# S3A6_Output_Signal_s_v1p00.net
KiCad netlist of a schematic drawn in EAGLE
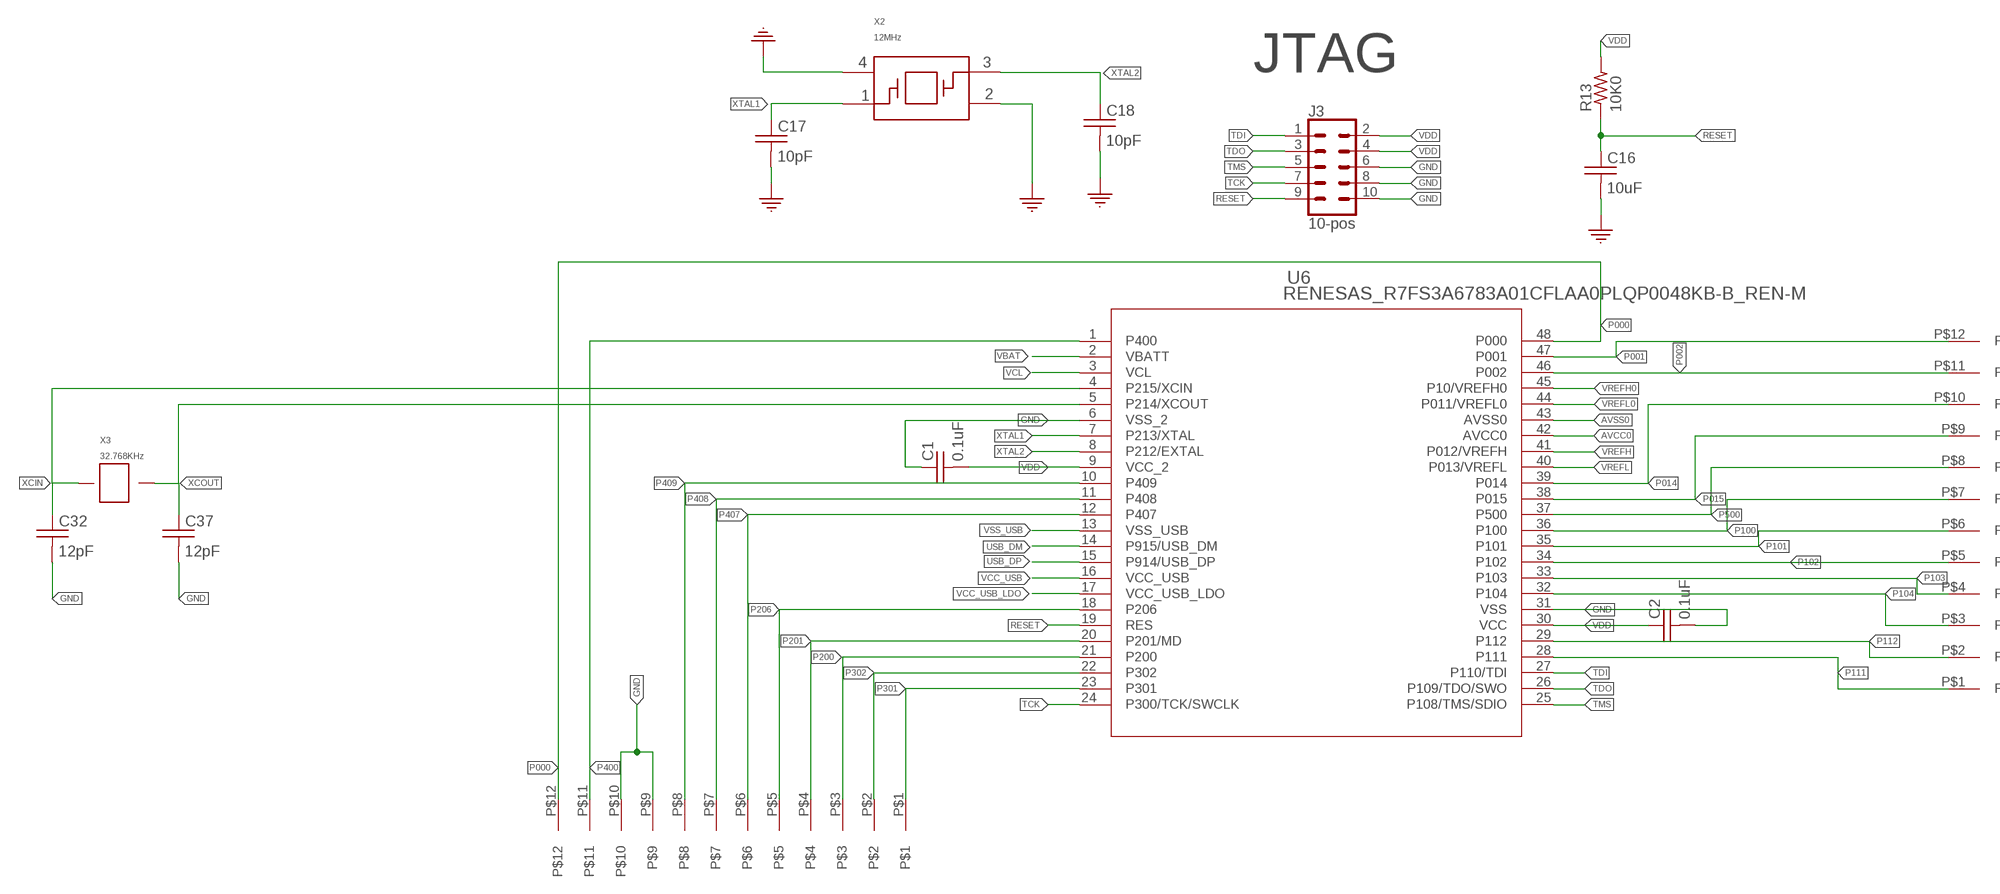
[diagram p0: schematic, sheet 1, part 1 of 2]
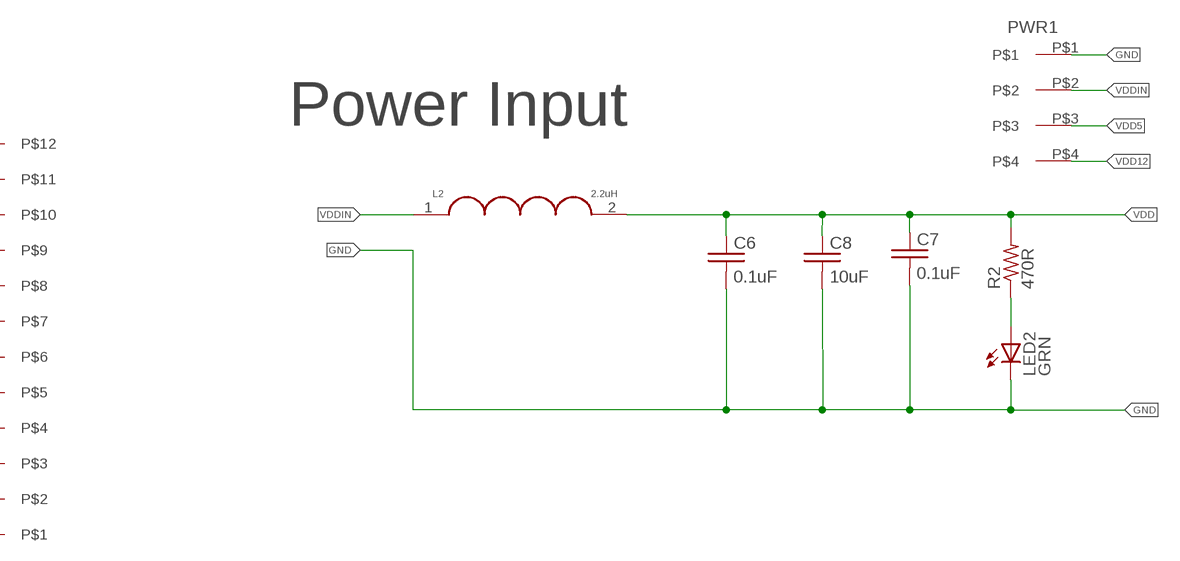
[diagram p1: schematic, sheet 1, part 2 of 2]

(export (version "E")
  (design (tool "Eeschema 10.0.6"))
  (components
    (comp (ref "C1")
      (value "0.1uF")
      (footprint "eagle-import:0402")
      (fields (field (name "PARTNO") "CL05F104ZO5NNNC"))
      (libsource (lib "eagle-import") (part "C_0402_0.1UF"))
    )
    (comp (ref "C2")
      (value "0.1uF")
      (footprint "eagle-import:0402")
      (fields (field (name "PARTNO") "CL05F104ZO5NNNC"))
      (libsource (lib "eagle-import") (part "C_0402_0.1UF"))
    )
    (comp (ref "C6")
      (value "0.1uF")
      (footprint "eagle-import:0402")
      (libsource (lib "eagle-import") (part "C_0402"))
    )
    (comp (ref "C7")
      (value "0.1uF")
      (footprint "eagle-import:0402")
      (libsource (lib "eagle-import") (part "C_0402"))
    )
    (comp (ref "C8")
      (value "10uF")
      (footprint "eagle-import:0402")
      (libsource (lib "eagle-import") (part "C_0402"))
    )
    (comp (ref "C16")
      (value "10uF")
      (footprint "eagle-import:0402")
      (fields (field (name "PARTNO") "CL05A106MP8NUB8"))
      (libsource (lib "eagle-import") (part "C_0402_10UF"))
    )
    (comp (ref "C17")
      (value "10pF")
      (footprint "eagle-import:0402")
      (fields (field (name "PARTNO") "UMK105CG180JV-F"))
      (libsource (lib "eagle-import") (part "C_0402_18PF"))
    )
    (comp (ref "C18")
      (value "10pF")
      (footprint "eagle-import:0402")
      (fields (field (name "PARTNO") "UMK105CG180JV-F"))
      (libsource (lib "eagle-import") (part "C_0402_18PF"))
    )
    (comp (ref "C32")
      (value "12pF")
      (footprint "eagle-import:0402")
      (fields (field (name "PARTNO") "CL05C120JB5NNNC"))
      (libsource (lib "eagle-import") (part "C_0402_12PF"))
    )
    (comp (ref "C37")
      (value "12pF")
      (footprint "eagle-import:0402")
      (fields (field (name "PARTNO") "CL05C120JB5NNNC"))
      (libsource (lib "eagle-import") (part "C_0402_12PF"))
    )
    (comp (ref "J3")
      (value "10-pos")
      (footprint "eagle-import:2X5")
      (fields (field (name "PARTNO") "PH2RA-10-UA"))
      (libsource (lib "eagle-import") (part "CONN_05X2_RAPTH"))
    )
    (comp (ref "L2")
      (value "2.2uH")
      (footprint "eagle-import:1008_(2520_METRIC)")
      (libsource (lib "eagle-import") (part "INDUCTOR_1008_2.2_MH_1.3A"))
    )
    (comp (ref "LED2")
      (value "LED_0805_GREEN")
      (footprint "eagle-import:LED_0805_GREEN")
      (libsource (lib "eagle-import") (part "LED_0805_GREEN"))
    )
    (comp (ref "PWR1")
      (value "4-pos")
      (footprint "eagle-import:1X4_3.81MM_PITCH")
      (fields (field (name "PARTNO") "691322310004"))
      (libsource (lib "eagle-import") (part "3.81MM_1_X_4_RT_ANGLE_PLUG_HEADER"))
    )
    (comp (ref "R2")
      (value "470R")
      (footprint "eagle-import:0402")
      (libsource (lib "eagle-import") (part "R_0402"))
    )
    (comp (ref "R13")
      (value "10K0")
      (footprint "eagle-import:0402")
      (fields (field (name "PARTNO") "RMCF0402JT10K0"))
      (libsource (lib "eagle-import") (part "R_0402_10K0"))
    )
    (comp (ref "U$1")
      (value "1_X_12_HEADER_GENERIC_.1INCH")
      (footprint "eagle-import:HEADER_1_X_12_.1_INCH")
      (libsource (lib "eagle-import") (part "1_X_12_HEADER_GENERIC_.1INCH"))
    )
    (comp (ref "U$2")
      (value "1_X_12_HEADER_GENERIC_.1INCH")
      (footprint "eagle-import:HEADER_1_X_12_.1_INCH")
      (libsource (lib "eagle-import") (part "1_X_12_HEADER_GENERIC_.1INCH"))
    )
    (comp (ref "U6")
      (value "RENESAS_R7FS3A6783A01CFLAA0PLQP0048KB-B_REN-M")
      (footprint "eagle-import:PLQP0048KB-B_REN-M")
      (fields
        (field (name "MANUFACTURER_PART_NUMBER") "R7FS3A6783A01CFL#AA0")
        (field (name "COPYRIGHT") "Copyright (C) 2021 Accelerated Designs. All rights reserved")
      )
      (libsource (lib "eagle-import") (part "RENESAS_R7FS3A6783A01CFLAA0PLQP0048KB-B_REN-M"))
    )
    (comp (ref "X2")
      (value "12MHz")
      (footprint "eagle-import:SMD_3225")
      (fields (field (name "PARTNO") "FA-238 24.0000MB-C3 "))
      (libsource (lib "eagle-import") (part "XTAL_24_MHZ"))
    )
    (comp (ref "X3")
      (value "32.768KHz")
      (footprint "eagle-import:SMD_X_2_PADS")
      (fields (field (name "PARTNO") "ABS07-32.768KHZ-T"))
      (libsource (lib "eagle-import") (part "XTAL_32.768KHZ"))
    )
  )
  (nets
    (net (code "1") (name "AVCC0") (class "Default")
      (node (ref "U6") (pin "42") (pinfunction "AVCC0_42") (pintype "power_in"))
    )
    (net (code "2") (name "AVSS0") (class "Default")
      (node (ref "U6") (pin "43") (pinfunction "AVSS0_43") (pintype "passive"))
    )
    (net (code "3") (name "GND") (class "Default")
      (node (ref "C1") (pin "P$1") (pinfunction "1_P$1") (pintype "passive"))
      (node (ref "C16") (pin "P$2") (pinfunction "2_P$2") (pintype "passive"))
      (node (ref "C17") (pin "P$2") (pinfunction "2_P$2") (pintype "passive"))
      (node (ref "C18") (pin "P$2") (pinfunction "2_P$2") (pintype "passive"))
      (node (ref "C2") (pin "P$2") (pinfunction "2_P$2") (pintype "passive"))
      (node (ref "C32") (pin "P$2") (pinfunction "2_P$2") (pintype "passive"))
      (node (ref "C37") (pin "P$2") (pinfunction "2_P$2") (pintype "passive"))
      (node (ref "C6") (pin "P$2") (pinfunction "2_P$2") (pintype "passive"))
      (node (ref "C7") (pin "P$2") (pinfunction "2_P$2") (pintype "passive"))
      (node (ref "C8") (pin "P$2") (pinfunction "2_P$2") (pintype "passive"))
      (node (ref "J3") (pin "10") (pinfunction "10_10") (pintype "passive"))
      (node (ref "J3") (pin "6") (pinfunction "6_6") (pintype "passive"))
      (node (ref "J3") (pin "8") (pinfunction "8_8") (pintype "passive"))
      (node (ref "LED2") (pin "C") (pinfunction "C_C") (pintype "passive"))
      (node (ref "PWR1") (pin "P$1") (pinfunction "P$1_P$1") (pintype "bidirectional"))
      (node (ref "U$1") (pin "P$10") (pinfunction "P$10_P$10") (pintype "bidirectional"))
      (node (ref "U$1") (pin "P$9") (pinfunction "P$9_P$9") (pintype "bidirectional"))
      (node (ref "U6") (pin "31") (pinfunction "VSS_31") (pintype "passive"))
      (node (ref "U6") (pin "6") (pinfunction "VSS_2_6") (pintype "passive"))
      (node (ref "X2") (pin "2") (pinfunction "2_2") (pintype "bidirectional"))
      (node (ref "X2") (pin "4") (pinfunction "4_4") (pintype "bidirectional"))
    )
    (net (code "4") (name "Net-(R2-1)") (class "Default")
      (node (ref "LED2") (pin "A") (pinfunction "A_A") (pintype "passive"))
      (node (ref "R2") (pin "P$1") (pinfunction "1_P$1") (pintype "passive"))
    )
    (net (code "5") (name "P000") (class "Default")
      (node (ref "U$1") (pin "P$12") (pinfunction "P$12_P$12") (pintype "bidirectional"))
      (node (ref "U6") (pin "48") (pinfunction "P000_48") (pintype "bidirectional"))
    )
    (net (code "6") (name "P001") (class "Default")
      (node (ref "U$2") (pin "P$12") (pinfunction "P$12_P$12") (pintype "bidirectional"))
      (node (ref "U6") (pin "47") (pinfunction "P001_47") (pintype "bidirectional"))
    )
    (net (code "7") (name "P002") (class "Default")
      (node (ref "U$2") (pin "P$11") (pinfunction "P$11_P$11") (pintype "bidirectional"))
      (node (ref "U6") (pin "46") (pinfunction "P002_46") (pintype "bidirectional"))
    )
    (net (code "8") (name "P014") (class "Default")
      (node (ref "U$2") (pin "P$10") (pinfunction "P$10_P$10") (pintype "bidirectional"))
      (node (ref "U6") (pin "39") (pinfunction "P014_39") (pintype "bidirectional"))
    )
    (net (code "9") (name "P015") (class "Default")
      (node (ref "U$2") (pin "P$9") (pinfunction "P$9_P$9") (pintype "bidirectional"))
      (node (ref "U6") (pin "38") (pinfunction "P015_38") (pintype "bidirectional"))
    )
    (net (code "10") (name "P100") (class "Default")
      (node (ref "U$2") (pin "P$7") (pinfunction "P$7_P$7") (pintype "bidirectional"))
      (node (ref "U6") (pin "36") (pinfunction "P100_36") (pintype "bidirectional"))
    )
    (net (code "11") (name "P101") (class "Default")
      (node (ref "U$2") (pin "P$6") (pinfunction "P$6_P$6") (pintype "bidirectional"))
      (node (ref "U6") (pin "35") (pinfunction "P101_35") (pintype "bidirectional"))
    )
    (net (code "12") (name "P102") (class "Default")
      (node (ref "U$2") (pin "P$5") (pinfunction "P$5_P$5") (pintype "bidirectional"))
      (node (ref "U6") (pin "34") (pinfunction "P102_34") (pintype "bidirectional"))
    )
    (net (code "13") (name "P103") (class "Default")
      (node (ref "U$2") (pin "P$4") (pinfunction "P$4_P$4") (pintype "bidirectional"))
      (node (ref "U6") (pin "33") (pinfunction "P103_33") (pintype "bidirectional"))
    )
    (net (code "14") (name "P104") (class "Default")
      (node (ref "U$2") (pin "P$3") (pinfunction "P$3_P$3") (pintype "bidirectional"))
      (node (ref "U6") (pin "32") (pinfunction "P104_32") (pintype "bidirectional"))
    )
    (net (code "15") (name "P111") (class "Default")
      (node (ref "U$2") (pin "P$1") (pinfunction "P$1_P$1") (pintype "bidirectional"))
      (node (ref "U6") (pin "28") (pinfunction "P111_28") (pintype "bidirectional"))
    )
    (net (code "16") (name "P112") (class "Default")
      (node (ref "U$2") (pin "P$2") (pinfunction "P$2_P$2") (pintype "bidirectional"))
      (node (ref "U6") (pin "29") (pinfunction "P112_29") (pintype "bidirectional"))
    )
    (net (code "17") (name "P200") (class "Default")
      (node (ref "U$1") (pin "P$3") (pinfunction "P$3_P$3") (pintype "bidirectional"))
      (node (ref "U6") (pin "21") (pinfunction "P200_21") (pintype "bidirectional"))
    )
    (net (code "18") (name "P201") (class "Default")
      (node (ref "U$1") (pin "P$4") (pinfunction "P$4_P$4") (pintype "bidirectional"))
      (node (ref "U6") (pin "20") (pinfunction "P201/MD_20") (pintype "bidirectional"))
    )
    (net (code "19") (name "P206") (class "Default")
      (node (ref "U$1") (pin "P$5") (pinfunction "P$5_P$5") (pintype "bidirectional"))
      (node (ref "U6") (pin "18") (pinfunction "P206_18") (pintype "bidirectional"))
    )
    (net (code "20") (name "P301") (class "Default")
      (node (ref "U$1") (pin "P$1") (pinfunction "P$1_P$1") (pintype "bidirectional"))
      (node (ref "U6") (pin "23") (pinfunction "P301_23") (pintype "bidirectional"))
    )
    (net (code "21") (name "P302") (class "Default")
      (node (ref "U$1") (pin "P$2") (pinfunction "P$2_P$2") (pintype "bidirectional"))
      (node (ref "U6") (pin "22") (pinfunction "P302_22") (pintype "bidirectional"))
    )
    (net (code "22") (name "P400") (class "Default")
      (node (ref "U$1") (pin "P$11") (pinfunction "P$11_P$11") (pintype "bidirectional"))
      (node (ref "U6") (pin "1") (pinfunction "P400_1") (pintype "bidirectional"))
    )
    (net (code "23") (name "P407") (class "Default")
      (node (ref "U$1") (pin "P$6") (pinfunction "P$6_P$6") (pintype "bidirectional"))
      (node (ref "U6") (pin "12") (pinfunction "P407_12") (pintype "bidirectional"))
    )
    (net (code "24") (name "P408") (class "Default")
      (node (ref "U$1") (pin "P$7") (pinfunction "P$7_P$7") (pintype "bidirectional"))
      (node (ref "U6") (pin "11") (pinfunction "P408_11") (pintype "bidirectional"))
    )
    (net (code "25") (name "P409") (class "Default")
      (node (ref "U$1") (pin "P$8") (pinfunction "P$8_P$8") (pintype "bidirectional"))
      (node (ref "U6") (pin "10") (pinfunction "P409_10") (pintype "bidirectional"))
    )
    (net (code "26") (name "P500") (class "Default")
      (node (ref "U$2") (pin "P$8") (pinfunction "P$8_P$8") (pintype "bidirectional"))
      (node (ref "U6") (pin "37") (pinfunction "P500_37") (pintype "bidirectional"))
    )
    (net (code "27") (name "RESET") (class "Default")
      (node (ref "C16") (pin "P$1") (pinfunction "1_P$1") (pintype "passive"))
      (node (ref "J3") (pin "9") (pinfunction "9_9") (pintype "passive"))
      (node (ref "R13") (pin "P$1") (pinfunction "1_P$1") (pintype "passive"))
      (node (ref "U6") (pin "19") (pinfunction "RES_19") (pintype "passive"))
    )
    (net (code "28") (name "TCK") (class "Default")
      (node (ref "J3") (pin "7") (pinfunction "7_7") (pintype "passive"))
      (node (ref "U6") (pin "24") (pinfunction "P300/TCK/SWCLK_24") (pintype "bidirectional"))
    )
    (net (code "29") (name "TDI") (class "Default")
      (node (ref "J3") (pin "1") (pinfunction "1_1") (pintype "passive"))
      (node (ref "U6") (pin "27") (pinfunction "P110/TDI_27") (pintype "bidirectional"))
    )
    (net (code "30") (name "TDO") (class "Default")
      (node (ref "J3") (pin "3") (pinfunction "3_3") (pintype "passive"))
      (node (ref "U6") (pin "26") (pinfunction "P109/TDO/SWO_26") (pintype "bidirectional"))
    )
    (net (code "31") (name "TMS") (class "Default")
      (node (ref "J3") (pin "5") (pinfunction "5_5") (pintype "passive"))
      (node (ref "U6") (pin "25") (pinfunction "P108/TMS/SDIO_25") (pintype "bidirectional"))
    )
    (net (code "32") (name "USB_DM") (class "Default")
      (node (ref "U6") (pin "14") (pinfunction "P915/USB_DM_14") (pintype "bidirectional"))
    )
    (net (code "33") (name "USB_DP") (class "Default")
      (node (ref "U6") (pin "15") (pinfunction "P914/USB_DP_15") (pintype "bidirectional"))
    )
    (net (code "34") (name "VBAT") (class "Default")
      (node (ref "U6") (pin "2") (pinfunction "VBATT_2") (pintype "passive"))
    )
    (net (code "35") (name "VCC_USB") (class "Default")
      (node (ref "U6") (pin "16") (pinfunction "VCC_USB_16") (pintype "power_in"))
    )
    (net (code "36") (name "VCC_USB_LDO") (class "Default")
      (node (ref "U6") (pin "17") (pinfunction "VCC_USB_LDO_17") (pintype "power_in"))
    )
    (net (code "37") (name "VCL") (class "Default")
      (node (ref "U6") (pin "3") (pinfunction "VCL_3") (pintype "passive"))
    )
    (net (code "38") (name "VDD") (class "Default")
      (node (ref "C1") (pin "P$2") (pinfunction "2_P$2") (pintype "passive"))
      (node (ref "C2") (pin "P$1") (pinfunction "1_P$1") (pintype "passive"))
      (node (ref "C6") (pin "P$1") (pinfunction "1_P$1") (pintype "passive"))
      (node (ref "C7") (pin "P$1") (pinfunction "1_P$1") (pintype "passive"))
      (node (ref "C8") (pin "P$1") (pinfunction "1_P$1") (pintype "passive"))
      (node (ref "J3") (pin "2") (pinfunction "2_2") (pintype "passive"))
      (node (ref "J3") (pin "4") (pinfunction "4_4") (pintype "passive"))
      (node (ref "L2") (pin "2") (pinfunction "P$2_2") (pintype "bidirectional"))
      (node (ref "R13") (pin "P$2") (pinfunction "2_P$2") (pintype "passive"))
      (node (ref "R2") (pin "P$2") (pinfunction "2_P$2") (pintype "passive"))
      (node (ref "U6") (pin "30") (pinfunction "VCC_30") (pintype "power_in"))
      (node (ref "U6") (pin "9") (pinfunction "VCC_2_9") (pintype "power_in"))
    )
    (net (code "39") (name "VDD5") (class "Default")
      (node (ref "PWR1") (pin "P$3") (pinfunction "P$3_P$3") (pintype "bidirectional"))
    )
    (net (code "40") (name "VDD12") (class "Default")
      (node (ref "PWR1") (pin "P$4") (pinfunction "P$4_P$4") (pintype "bidirectional"))
    )
    (net (code "41") (name "VDDIN") (class "Default")
      (node (ref "L2") (pin "1") (pinfunction "P$1_1") (pintype "bidirectional"))
      (node (ref "PWR1") (pin "P$2") (pinfunction "P$2_P$2") (pintype "bidirectional"))
    )
    (net (code "42") (name "VREFH") (class "Default")
      (node (ref "U6") (pin "41") (pinfunction "P012/VREFH_41") (pintype "power_in"))
    )
    (net (code "43") (name "VREFH0") (class "Default")
      (node (ref "U6") (pin "45") (pinfunction "P10/VREFH0_45") (pintype "power_in"))
    )
    (net (code "44") (name "VREFL") (class "Default")
      (node (ref "U6") (pin "40") (pinfunction "P013/VREFL_40") (pintype "power_in"))
    )
    (net (code "45") (name "VREFL0") (class "Default")
      (node (ref "U6") (pin "44") (pinfunction "P011/VREFL0_44") (pintype "power_in"))
    )
    (net (code "46") (name "VSS_USB") (class "Default")
      (node (ref "U6") (pin "13") (pinfunction "VSS_USB_13") (pintype "passive"))
    )
    (net (code "47") (name "XCIN") (class "Default")
      (node (ref "C32") (pin "P$1") (pinfunction "1_P$1") (pintype "passive"))
      (node (ref "U6") (pin "4") (pinfunction "P215/XCIN_4") (pintype "bidirectional"))
      (node (ref "X3") (pin "P$1") (pinfunction "P$1_P$1") (pintype "bidirectional"))
    )
    (net (code "48") (name "XCOUT") (class "Default")
      (node (ref "C37") (pin "P$1") (pinfunction "1_P$1") (pintype "passive"))
      (node (ref "U6") (pin "5") (pinfunction "P214/XCOUT_5") (pintype "output"))
      (node (ref "X3") (pin "P$2") (pinfunction "P$2_P$2") (pintype "bidirectional"))
    )
    (net (code "49") (name "XTAL1") (class "Default")
      (node (ref "C17") (pin "P$1") (pinfunction "1_P$1") (pintype "passive"))
      (node (ref "U6") (pin "7") (pinfunction "P213/XTAL_7") (pintype "bidirectional"))
      (node (ref "X2") (pin "1") (pinfunction "1_1") (pintype "bidirectional"))
    )
    (net (code "50") (name "XTAL2") (class "Default")
      (node (ref "C18") (pin "P$1") (pinfunction "1_P$1") (pintype "passive"))
      (node (ref "U6") (pin "8") (pinfunction "P212/EXTAL_8") (pintype "bidirectional"))
      (node (ref "X2") (pin "3") (pinfunction "3_3") (pintype "bidirectional"))
    )
  )
)
